# 1541_Multi-ROM_Rev1_1.net
KiCad netlist of a schematic drawn in EAGLE
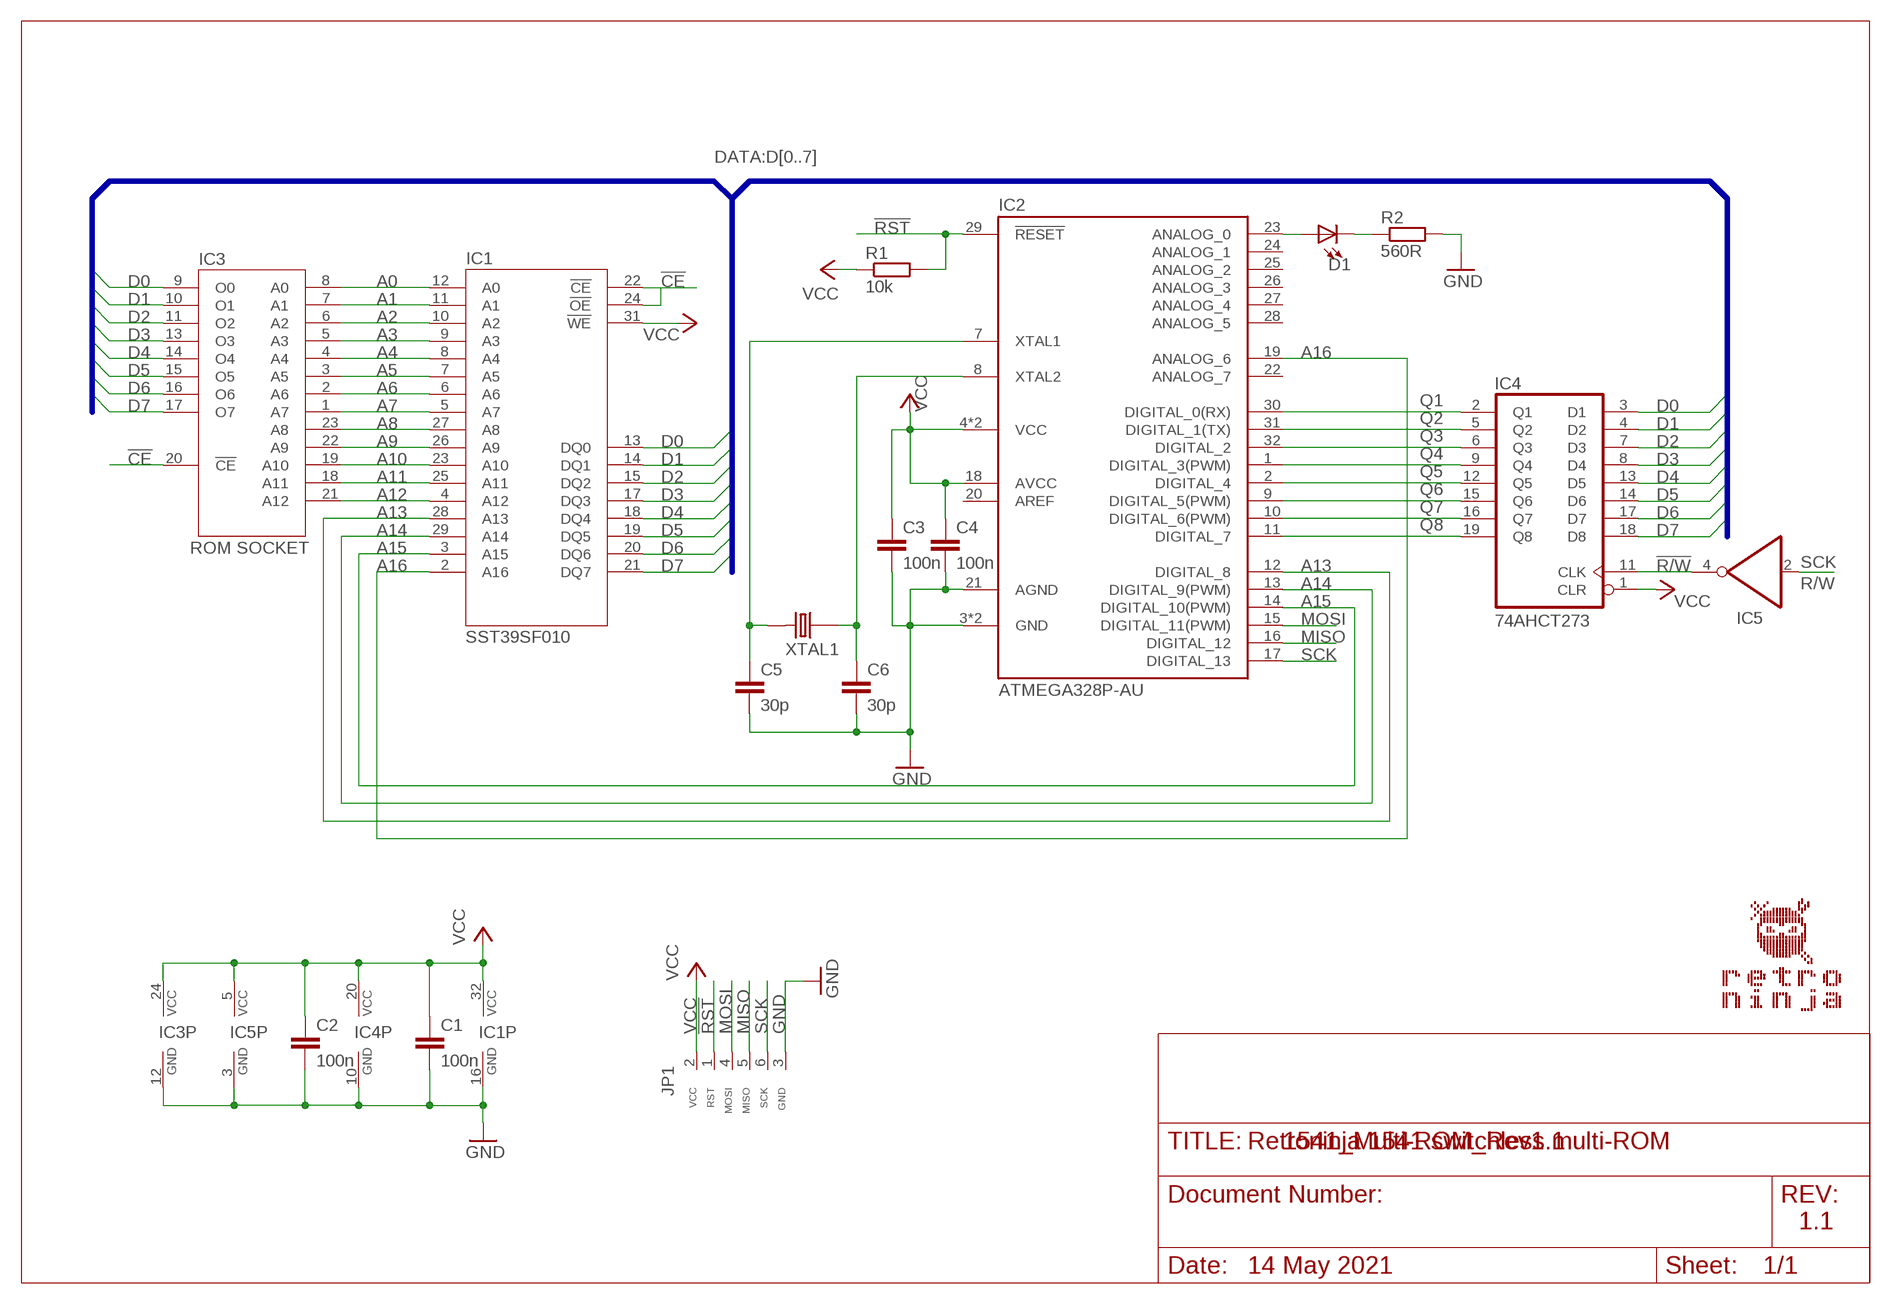
[diagram p0: schematic, sheet 1]

(export (version "E")
  (design (tool "Eeschema 10.0.6"))
  (components
    (comp (ref "C1")
      (value "100n")
      (footprint "eagle-import:C0805")
      (libsource (lib "eagle-import") (part "C-EUC0805"))
    )
    (comp (ref "C2")
      (value "100n")
      (footprint "eagle-import:C0805")
      (libsource (lib "eagle-import") (part "C-EUC0805"))
    )
    (comp (ref "C3")
      (value "100n")
      (footprint "eagle-import:C0805")
      (libsource (lib "eagle-import") (part "C-EUC0805"))
    )
    (comp (ref "C4")
      (value "100n")
      (footprint "eagle-import:C0805")
      (libsource (lib "eagle-import") (part "C-EUC0805"))
    )
    (comp (ref "C5")
      (value "30p")
      (footprint "eagle-import:C0805")
      (libsource (lib "eagle-import") (part "C-EUC0805"))
    )
    (comp (ref "C6")
      (value "30p")
      (footprint "eagle-import:C0805")
      (libsource (lib "eagle-import") (part "C-EUC0805"))
    )
    (comp (ref "D1")
      (value "LED_0805")
      (footprint "eagle-import:LED0805")
      (libsource (lib "eagle-import") (part "LED_0805"))
    )
    (comp (ref "IC1")
      (value "SST39SF010")
      (footprint "eagle-import:PLCC32_SHORT")
      (libsource (lib "eagle-import") (part "SST39XX010_PLCC_SHORT"))
    )
    (comp (ref "IC2")
      (value "ATMEGA328P-AU")
      (footprint "eagle-import:TQFP32")
      (libsource (lib "eagle-import") (part "ARDUINO_168_328_TQFP"))
    )
    (comp (ref "IC3")
      (value "ROM SOCKET")
      (footprint "eagle-import:DIL24-6_DOWNPINS")
      (libsource (lib "eagle-import") (part "2364_DOWNPINS"))
    )
    (comp (ref "IC4")
      (value "74AHCT273")
      (footprint "eagle-import:SO20")
      (libsource (lib "eagle-import") (part "74273NS"))
    )
    (comp (ref "IC5")
      (value "741G04_SOT23")
      (footprint "eagle-import:SOT23-5")
      (libsource (lib "eagle-import") (part "741G04_SOT23"))
    )
    (comp (ref "JP1")
      (value "ICSP_CONNECTOR_TL866_RIGHT2")
      (footprint "eagle-import:HEADER_1X6_RIGHT")
      (libsource (lib "eagle-import") (part "ICSP_CONNECTOR_TL866_RIGHT2"))
    )
    (comp (ref "R1")
      (value "10k")
      (footprint "eagle-import:R0805")
      (libsource (lib "eagle-import") (part "R-EU_R0805"))
    )
    (comp (ref "R2")
      (value "560R")
      (footprint "eagle-import:R0805")
      (libsource (lib "eagle-import") (part "R-EU_R0805"))
    )
    (comp (ref "XTAL1")
      (value "CRYSTAL")
      (footprint "eagle-import:CRYSTAL_SMD-2_7X4X2.3")
      (libsource (lib "eagle-import") (part "CRYSTAL"))
    )
  )
  (nets
    (net (code "9") (name "/A0") (class "Default")
      (node (ref "IC1") (pin "12") (pinfunction "A0_12") (pintype "input"))
      (node (ref "IC3") (pin "8") (pinfunction "A0_8") (pintype "input"))
    )
    (net (code "10") (name "/A1") (class "Default")
      (node (ref "IC1") (pin "11") (pinfunction "A1_11") (pintype "input"))
      (node (ref "IC3") (pin "7") (pinfunction "A1_7") (pintype "input"))
    )
    (net (code "11") (name "/A2") (class "Default")
      (node (ref "IC1") (pin "10") (pinfunction "A2_10") (pintype "input"))
      (node (ref "IC3") (pin "6") (pinfunction "A2_6") (pintype "input"))
    )
    (net (code "12") (name "/A3") (class "Default")
      (node (ref "IC1") (pin "9") (pinfunction "A3_9") (pintype "input"))
      (node (ref "IC3") (pin "5") (pinfunction "A3_5") (pintype "input"))
    )
    (net (code "13") (name "/A4") (class "Default")
      (node (ref "IC1") (pin "8") (pinfunction "A4_8") (pintype "input"))
      (node (ref "IC3") (pin "4") (pinfunction "A4_4") (pintype "input"))
    )
    (net (code "14") (name "/A5") (class "Default")
      (node (ref "IC1") (pin "7") (pinfunction "A5_7") (pintype "input"))
      (node (ref "IC3") (pin "3") (pinfunction "A5_3") (pintype "input"))
    )
    (net (code "15") (name "/A6") (class "Default")
      (node (ref "IC1") (pin "6") (pinfunction "A6_6") (pintype "input"))
      (node (ref "IC3") (pin "2") (pinfunction "A6_2") (pintype "input"))
    )
    (net (code "16") (name "/A7") (class "Default")
      (node (ref "IC1") (pin "5") (pinfunction "A7_5") (pintype "input"))
      (node (ref "IC3") (pin "1") (pinfunction "A7_1") (pintype "input"))
    )
    (net (code "17") (name "/A8") (class "Default")
      (node (ref "IC1") (pin "27") (pinfunction "A8_27") (pintype "input"))
      (node (ref "IC3") (pin "23") (pinfunction "A8_23") (pintype "input"))
    )
    (net (code "18") (name "/A9") (class "Default")
      (node (ref "IC1") (pin "26") (pinfunction "A9_26") (pintype "input"))
      (node (ref "IC3") (pin "22") (pinfunction "A9_22") (pintype "input"))
    )
    (net (code "19") (name "/A10") (class "Default")
      (node (ref "IC1") (pin "23") (pinfunction "A10_23") (pintype "input"))
      (node (ref "IC3") (pin "19") (pinfunction "A10_19") (pintype "input"))
    )
    (net (code "20") (name "/A11") (class "Default")
      (node (ref "IC1") (pin "25") (pinfunction "A11_25") (pintype "input"))
      (node (ref "IC3") (pin "18") (pinfunction "A11_18") (pintype "input"))
    )
    (net (code "21") (name "/A12") (class "Default")
      (node (ref "IC1") (pin "4") (pinfunction "A12_4") (pintype "input"))
      (node (ref "IC3") (pin "21") (pinfunction "A12_21") (pintype "input"))
    )
    (net (code "22") (name "/A13") (class "Default")
      (node (ref "IC1") (pin "28") (pinfunction "A13_28") (pintype "input"))
      (node (ref "IC2") (pin "12") (pinfunction "DIGITAL_8_12") (pintype "bidirectional"))
    )
    (net (code "23") (name "/A14") (class "Default")
      (node (ref "IC1") (pin "29") (pinfunction "A14_29") (pintype "input"))
      (node (ref "IC2") (pin "13") (pinfunction "DIGITAL_9(PWM)_13") (pintype "bidirectional"))
    )
    (net (code "24") (name "/A15") (class "Default")
      (node (ref "IC1") (pin "3") (pinfunction "A15_3") (pintype "input"))
      (node (ref "IC2") (pin "14") (pinfunction "DIGITAL_10(PWM)_14") (pintype "bidirectional"))
    )
    (net (code "25") (name "/A16") (class "Default")
      (node (ref "IC1") (pin "2") (pinfunction "A16_2") (pintype "input"))
      (node (ref "IC2") (pin "19") (pinfunction "ANALOG_6_19") (pintype "bidirectional"))
    )
    (net (code "26") (name "/D0") (class "Default")
      (node (ref "IC1") (pin "13") (pinfunction "DQ0_13") (pintype "bidirectional"))
      (node (ref "IC3") (pin "9") (pinfunction "O0_9") (pintype "tri_state"))
      (node (ref "IC4") (pin "3") (pinfunction "D1_3") (pintype "input"))
    )
    (net (code "27") (name "/D1") (class "Default")
      (node (ref "IC1") (pin "14") (pinfunction "DQ1_14") (pintype "bidirectional"))
      (node (ref "IC3") (pin "10") (pinfunction "O1_10") (pintype "tri_state"))
      (node (ref "IC4") (pin "4") (pinfunction "D2_4") (pintype "input"))
    )
    (net (code "28") (name "/D2") (class "Default")
      (node (ref "IC1") (pin "15") (pinfunction "DQ2_15") (pintype "bidirectional"))
      (node (ref "IC3") (pin "11") (pinfunction "O2_11") (pintype "tri_state"))
      (node (ref "IC4") (pin "7") (pinfunction "D3_7") (pintype "input"))
    )
    (net (code "29") (name "/D3") (class "Default")
      (node (ref "IC1") (pin "17") (pinfunction "DQ3_17") (pintype "bidirectional"))
      (node (ref "IC3") (pin "13") (pinfunction "O3_13") (pintype "tri_state"))
      (node (ref "IC4") (pin "8") (pinfunction "D4_8") (pintype "input"))
    )
    (net (code "30") (name "/D4") (class "Default")
      (node (ref "IC1") (pin "18") (pinfunction "DQ4_18") (pintype "bidirectional"))
      (node (ref "IC3") (pin "14") (pinfunction "O4_14") (pintype "tri_state"))
      (node (ref "IC4") (pin "13") (pinfunction "D5_13") (pintype "input"))
    )
    (net (code "31") (name "/D5") (class "Default")
      (node (ref "IC1") (pin "19") (pinfunction "DQ5_19") (pintype "bidirectional"))
      (node (ref "IC3") (pin "15") (pinfunction "O5_15") (pintype "tri_state"))
      (node (ref "IC4") (pin "14") (pinfunction "D6_14") (pintype "input"))
    )
    (net (code "32") (name "/D6") (class "Default")
      (node (ref "IC1") (pin "20") (pinfunction "DQ6_20") (pintype "bidirectional"))
      (node (ref "IC3") (pin "16") (pinfunction "O6_16") (pintype "tri_state"))
      (node (ref "IC4") (pin "17") (pinfunction "D7_17") (pintype "input"))
    )
    (net (code "33") (name "/D7") (class "Default")
      (node (ref "IC1") (pin "21") (pinfunction "DQ7_21") (pintype "bidirectional"))
      (node (ref "IC3") (pin "17") (pinfunction "O7_17") (pintype "tri_state"))
      (node (ref "IC4") (pin "18") (pinfunction "D8_18") (pintype "input"))
    )
    (net (code "35") (name "/MISO") (class "Default")
      (node (ref "IC2") (pin "16") (pinfunction "DIGITAL_12_16") (pintype "bidirectional"))
      (node (ref "JP1") (pin "5") (pinfunction "MISO_5") (pintype "output"))
    )
    (net (code "36") (name "/MOSI") (class "Default")
      (node (ref "IC2") (pin "15") (pinfunction "DIGITAL_11(PWM)_15") (pintype "bidirectional"))
      (node (ref "JP1") (pin "4") (pinfunction "MOSI_4") (pintype "input"))
    )
    (net (code "37") (name "/Q1") (class "Default")
      (node (ref "IC2") (pin "30") (pinfunction "DIGITAL_0(RX)_30") (pintype "bidirectional"))
      (node (ref "IC4") (pin "2") (pinfunction "Q1_2") (pintype "output"))
    )
    (net (code "38") (name "/Q2") (class "Default")
      (node (ref "IC2") (pin "31") (pinfunction "DIGITAL_1(TX)_31") (pintype "bidirectional"))
      (node (ref "IC4") (pin "5") (pinfunction "Q2_5") (pintype "output"))
    )
    (net (code "39") (name "/Q3") (class "Default")
      (node (ref "IC2") (pin "32") (pinfunction "DIGITAL_2_32") (pintype "bidirectional"))
      (node (ref "IC4") (pin "6") (pinfunction "Q3_6") (pintype "output"))
    )
    (net (code "40") (name "/Q4") (class "Default")
      (node (ref "IC2") (pin "1") (pinfunction "DIGITAL_3(PWM)_1") (pintype "bidirectional"))
      (node (ref "IC4") (pin "9") (pinfunction "Q4_9") (pintype "output"))
    )
    (net (code "41") (name "/Q5") (class "Default")
      (node (ref "IC2") (pin "2") (pinfunction "DIGITAL_4_2") (pintype "bidirectional"))
      (node (ref "IC4") (pin "12") (pinfunction "Q5_12") (pintype "output"))
    )
    (net (code "42") (name "/Q6") (class "Default")
      (node (ref "IC2") (pin "9") (pinfunction "DIGITAL_5(PWM)_9") (pintype "bidirectional"))
      (node (ref "IC4") (pin "15") (pinfunction "Q6_15") (pintype "output"))
    )
    (net (code "43") (name "/Q7") (class "Default")
      (node (ref "IC2") (pin "10") (pinfunction "DIGITAL_6(PWM)_10") (pintype "bidirectional"))
      (node (ref "IC4") (pin "16") (pinfunction "Q7_16") (pintype "output"))
    )
    (net (code "44") (name "/Q8") (class "Default")
      (node (ref "IC2") (pin "11") (pinfunction "DIGITAL_7_11") (pintype "bidirectional"))
      (node (ref "IC4") (pin "19") (pinfunction "Q8_19") (pintype "output"))
    )
    (net (code "45") (name "/SCK") (class "Default")
      (node (ref "IC2") (pin "17") (pinfunction "DIGITAL_13_17") (pintype "bidirectional"))
      (node (ref "IC5") (pin "2") (pinfunction "I_2") (pintype "input"))
      (node (ref "JP1") (pin "6") (pinfunction "SCK_6") (pintype "input"))
    )
    (net (code "46") (name "/~{CE}") (class "Default")
      (node (ref "IC1") (pin "22") (pinfunction "~{CE}_22") (pintype "input"))
      (node (ref "IC3") (pin "20") (pinfunction "~{CE}_20") (pintype "input"))
    )
    (net (code "47") (name "/~{RST}") (class "Default")
      (node (ref "IC2") (pin "29") (pinfunction "~{RESET}_29") (pintype "bidirectional"))
      (node (ref "JP1") (pin "1") (pinfunction "RST_1") (pintype "input"))
      (node (ref "R1") (pin "2") (pinfunction "2_2") (pintype "passive"))
    )
    (net (code "48") (name "/~{R{slash}W}") (class "Default")
      (node (ref "IC4") (pin "11") (pinfunction "CLK_11") (pintype "input"))
      (node (ref "IC5") (pin "4") (pinfunction "O_4") (pintype "output"))
    )
    (net (code "49") (name "GND") (class "Default")
      (node (ref "C1") (pin "2") (pinfunction "2_2") (pintype "passive"))
      (node (ref "C2") (pin "2") (pinfunction "2_2") (pintype "passive"))
      (node (ref "C3") (pin "2") (pinfunction "2_2") (pintype "passive"))
      (node (ref "C4") (pin "2") (pinfunction "2_2") (pintype "passive"))
      (node (ref "C5") (pin "2") (pinfunction "2_2") (pintype "passive"))
      (node (ref "C6") (pin "2") (pinfunction "2_2") (pintype "passive"))
      (node (ref "IC1") (pin "16") (pinfunction "GND_16") (pintype "power_in"))
      (node (ref "IC2") (pin "21") (pinfunction "AGND_21") (pintype "passive"))
      (node (ref "IC2") (pin "3") (pinfunction "GND_3") (pintype "passive"))
      (node (ref "IC2") (pin "5") (pinfunction "GND_5") (pintype "passive"))
      (node (ref "IC3") (pin "12") (pinfunction "GND_12") (pintype "power_in"))
      (node (ref "IC4") (pin "10") (pinfunction "GND_10") (pintype "power_in"))
      (node (ref "IC5") (pin "3") (pinfunction "GND_3") (pintype "power_in"))
      (node (ref "JP1") (pin "3") (pinfunction "GND_3") (pintype "power_in"))
      (node (ref "R2") (pin "2") (pinfunction "2_2") (pintype "passive"))
    )
    (net (code "50") (name "Net-(D1-PadC)") (class "Default")
      (node (ref "D1") (pin "C") (pinfunction "C_C") (pintype "passive"))
      (node (ref "R2") (pin "1") (pinfunction "1_1") (pintype "passive"))
    )
    (net (code "51") (name "Net-(IC2-ANALOG_0)") (class "Default")
      (node (ref "D1") (pin "A") (pinfunction "A_A") (pintype "passive"))
      (node (ref "IC2") (pin "23") (pinfunction "ANALOG_0_23") (pintype "bidirectional"))
    )
    (net (code "52") (name "Net-(IC2-XTAL1)") (class "Default")
      (node (ref "C5") (pin "1") (pinfunction "1_1") (pintype "passive"))
      (node (ref "IC2") (pin "7") (pinfunction "XTAL1_7") (pintype "bidirectional"))
      (node (ref "XTAL1") (pin "2") (pinfunction "2_2") (pintype "passive"))
    )
    (net (code "53") (name "Net-(IC2-XTAL2)") (class "Default")
      (node (ref "C6") (pin "1") (pinfunction "1_1") (pintype "passive"))
      (node (ref "IC2") (pin "8") (pinfunction "XTAL2_8") (pintype "bidirectional"))
      (node (ref "XTAL1") (pin "1") (pinfunction "1_1") (pintype "passive"))
    )
    (net (code "54") (name "VCC") (class "Default")
      (node (ref "C1") (pin "1") (pinfunction "1_1") (pintype "passive"))
      (node (ref "C2") (pin "1") (pinfunction "1_1") (pintype "passive"))
      (node (ref "C3") (pin "1") (pinfunction "1_1") (pintype "passive"))
      (node (ref "C4") (pin "1") (pinfunction "1_1") (pintype "passive"))
      (node (ref "IC1") (pin "31") (pinfunction "~{WE}_31") (pintype "input"))
      (node (ref "IC1") (pin "32") (pinfunction "VCC_32") (pintype "power_in"))
      (node (ref "IC2") (pin "18") (pinfunction "AVCC_18") (pintype "passive"))
      (node (ref "IC2") (pin "4") (pinfunction "VCC_4") (pintype "passive"))
      (node (ref "IC2") (pin "6") (pinfunction "VCC_6") (pintype "passive"))
      (node (ref "IC3") (pin "24") (pinfunction "VCC_24") (pintype "power_in"))
      (node (ref "IC4") (pin "1") (pinfunction "CLR_1") (pintype "input"))
      (node (ref "IC4") (pin "20") (pinfunction "VCC_20") (pintype "power_in"))
      (node (ref "IC5") (pin "5") (pinfunction "VCC_5") (pintype "power_in"))
      (node (ref "JP1") (pin "2") (pinfunction "VCC_2") (pintype "power_in"))
      (node (ref "R1") (pin "1") (pinfunction "1_1") (pintype "passive"))
    )
    (net (code "55") (name "unconnected-(IC1A-~{OE}-Pad24)") (class "Default")
      (node (ref "IC1") (pin "24") (pinfunction "~{OE}_24") (pintype "input"))
    )
    (net (code "56") (name "unconnected-(IC2-ANALOG_1-Pad24)") (class "Default")
      (node (ref "IC2") (pin "24") (pinfunction "ANALOG_1_24") (pintype "bidirectional"))
    )
    (net (code "57") (name "unconnected-(IC2-ANALOG_2-Pad25)") (class "Default")
      (node (ref "IC2") (pin "25") (pinfunction "ANALOG_2_25") (pintype "bidirectional"))
    )
    (net (code "58") (name "unconnected-(IC2-ANALOG_3-Pad26)") (class "Default")
      (node (ref "IC2") (pin "26") (pinfunction "ANALOG_3_26") (pintype "bidirectional"))
    )
    (net (code "59") (name "unconnected-(IC2-ANALOG_4-Pad27)") (class "Default")
      (node (ref "IC2") (pin "27") (pinfunction "ANALOG_4_27") (pintype "bidirectional"))
    )
    (net (code "60") (name "unconnected-(IC2-ANALOG_5-Pad28)") (class "Default")
      (node (ref "IC2") (pin "28") (pinfunction "ANALOG_5_28") (pintype "bidirectional"))
    )
    (net (code "61") (name "unconnected-(IC2-ANALOG_7-Pad22)") (class "Default")
      (node (ref "IC2") (pin "22") (pinfunction "ANALOG_7_22") (pintype "bidirectional"))
    )
    (net (code "62") (name "unconnected-(IC2-AREF-Pad20)") (class "Default")
      (node (ref "IC2") (pin "20") (pinfunction "AREF_20") (pintype "passive"))
    )
  )
)
